# FRAM.net
KiCad netlist of a schematic drawn in Altium Designer
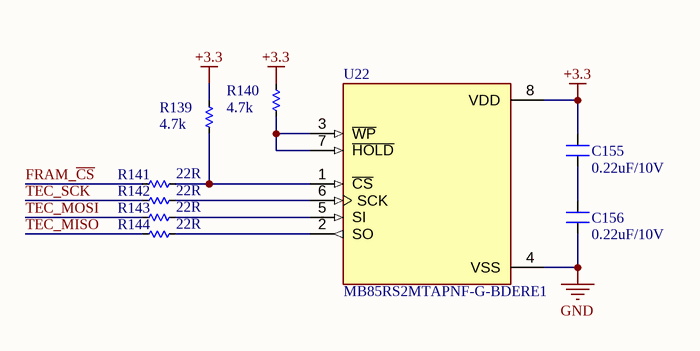
[diagram p0: FRAM.SchDoc]

(export (version "E")
  (design (tool "Eeschema 10.0.6"))
  (components
    (comp (ref "C155")
      (value "0.22uF/10V")
      (footprint "CAP_C_1608X80")
      (libsource (lib "Sang_library") (part "Capacitors"))
    )
    (comp (ref "C156")
      (value "0.22uF/10V")
      (footprint "CAP_C_1608X80")
      (libsource (lib "Sang_library") (part "Capacitors"))
    )
    (comp (ref "R139")
      (value "4.7k")
      (footprint "RES_C_1608X60")
      (description "SMD")
      (fields
        (field (name "MANUFACTURER") "Generic Components")
        (field (name "PUBLISHER") "Altium Hobart Technology Centre")
      )
      (libsource (lib "Sang_library") (part "Res SMD"))
    )
    (comp (ref "R140")
      (value "4.7k")
      (footprint "RES_C_1608X60")
      (description "SMD")
      (fields
        (field (name "MANUFACTURER") "Generic Components")
        (field (name "PUBLISHER") "Altium Hobart Technology Centre")
      )
      (libsource (lib "Sang_library") (part "Res SMD"))
    )
    (comp (ref "R141")
      (value "22R")
      (footprint "RES_C_1608X60")
      (description "SMD")
      (fields
        (field (name "MANUFACTURER") "Generic Components")
        (field (name "PUBLISHER") "Altium Hobart Technology Centre")
      )
      (libsource (lib "Sang_library") (part "Res SMD"))
    )
    (comp (ref "R142")
      (value "22R")
      (footprint "RES_C_1608X60")
      (description "SMD")
      (fields
        (field (name "MANUFACTURER") "Generic Components")
        (field (name "PUBLISHER") "Altium Hobart Technology Centre")
      )
      (libsource (lib "Sang_library") (part "Res SMD"))
    )
    (comp (ref "R143")
      (value "22R")
      (footprint "RES_C_1608X60")
      (description "SMD")
      (fields
        (field (name "MANUFACTURER") "Generic Components")
        (field (name "PUBLISHER") "Altium Hobart Technology Centre")
      )
      (libsource (lib "Sang_library") (part "Res SMD"))
    )
    (comp (ref "R144")
      (value "22R")
      (footprint "RES_C_1608X60")
      (description "SMD")
      (fields
        (field (name "MANUFACTURER") "Generic Components")
        (field (name "PUBLISHER") "Altium Hobart Technology Centre")
      )
      (libsource (lib "Sang_library") (part "Res SMD"))
    )
    (comp (ref "U22")
      (value "MB85RS2MTAPNF-G-BDERE1")
      (footprint "MB85RS2MTAPNF-G-BDERE1")
      (description "FRAM _Ferroelectric RAM_ Memory IC 2Mb _256K x 8_ SPI 40MHz 8-SOP")
      (fields (field (name "MF") "Fujitsu Electronics") (field (name "DIGI-KEY_PART_NUMBER") "865-1286-1-ND"))
      (libsource (lib "EXP_HW_V2") (part "MB85RS2MTAPNF-G-BDERE1"))
    )
  )
  (nets
    (net (code "1") (name "+3.3") (class "Default")
      (node (ref "C155") (pin "2") (pinfunction "2_2") (pintype "passive"))
      (node (ref "R139") (pin "1") (pinfunction "1_1") (pintype "passive"))
      (node (ref "R140") (pin "1") (pinfunction "1_1") (pintype "passive"))
      (node (ref "U22") (pin "8") (pinfunction "VDD_8") (pintype "power_in"))
    )
    (net (code "2") (name "/FRAM_~{CS}") (class "Default")
      (node (ref "R141") (pin "1") (pinfunction "1_1") (pintype "passive"))
    )
    (net (code "3") (name "/TEC_MISO") (class "Default")
      (node (ref "R144") (pin "1") (pinfunction "1_1") (pintype "passive"))
    )
    (net (code "4") (name "/TEC_MOSI") (class "Default")
      (node (ref "R143") (pin "1") (pinfunction "1_1") (pintype "passive"))
    )
    (net (code "5") (name "/TEC_SCK") (class "Default")
      (node (ref "R142") (pin "1") (pinfunction "1_1") (pintype "passive"))
    )
    (net (code "6") (name "GND") (class "Default")
      (node (ref "C156") (pin "1") (pinfunction "1_1") (pintype "passive"))
      (node (ref "U22") (pin "4") (pinfunction "VSS_4") (pintype "power_in"))
    )
    (net (code "7") (name "Net-(C155-Pad1)") (class "Default")
      (node (ref "C155") (pin "1") (pinfunction "1_1") (pintype "passive"))
      (node (ref "C156") (pin "2") (pinfunction "2_2") (pintype "passive"))
    )
    (net (code "8") (name "Net-(U22-SCK)") (class "Default")
      (node (ref "R142") (pin "2") (pinfunction "2_2") (pintype "passive"))
      (node (ref "U22") (pin "6") (pinfunction "SCK_6") (pintype "input"))
    )
    (net (code "9") (name "Net-(U22-SI)") (class "Default")
      (node (ref "R143") (pin "2") (pinfunction "2_2") (pintype "passive"))
      (node (ref "U22") (pin "5") (pinfunction "SI_5") (pintype "input"))
    )
    (net (code "10") (name "Net-(U22-SO)") (class "Default")
      (node (ref "R144") (pin "2") (pinfunction "2_2") (pintype "passive"))
      (node (ref "U22") (pin "2") (pinfunction "SO_2") (pintype "output"))
    )
    (net (code "11") (name "Net-(U22-~{CS})") (class "Default")
      (node (ref "R139") (pin "2") (pinfunction "2_2") (pintype "passive"))
      (node (ref "R141") (pin "2") (pinfunction "2_2") (pintype "passive"))
      (node (ref "U22") (pin "1") (pinfunction "~{CS}_1") (pintype "input"))
    )
    (net (code "12") (name "Net-(U22-~{HOLD})") (class "Default")
      (node (ref "R140") (pin "2") (pinfunction "2_2") (pintype "passive"))
      (node (ref "U22") (pin "3") (pinfunction "~{WP}_3") (pintype "input"))
      (node (ref "U22") (pin "7") (pinfunction "~{HOLD}_7") (pintype "input"))
    )
  )
)
